# PCB_Telemetria_2020.net
KiCad netlist of a schematic drawn in EAGLE
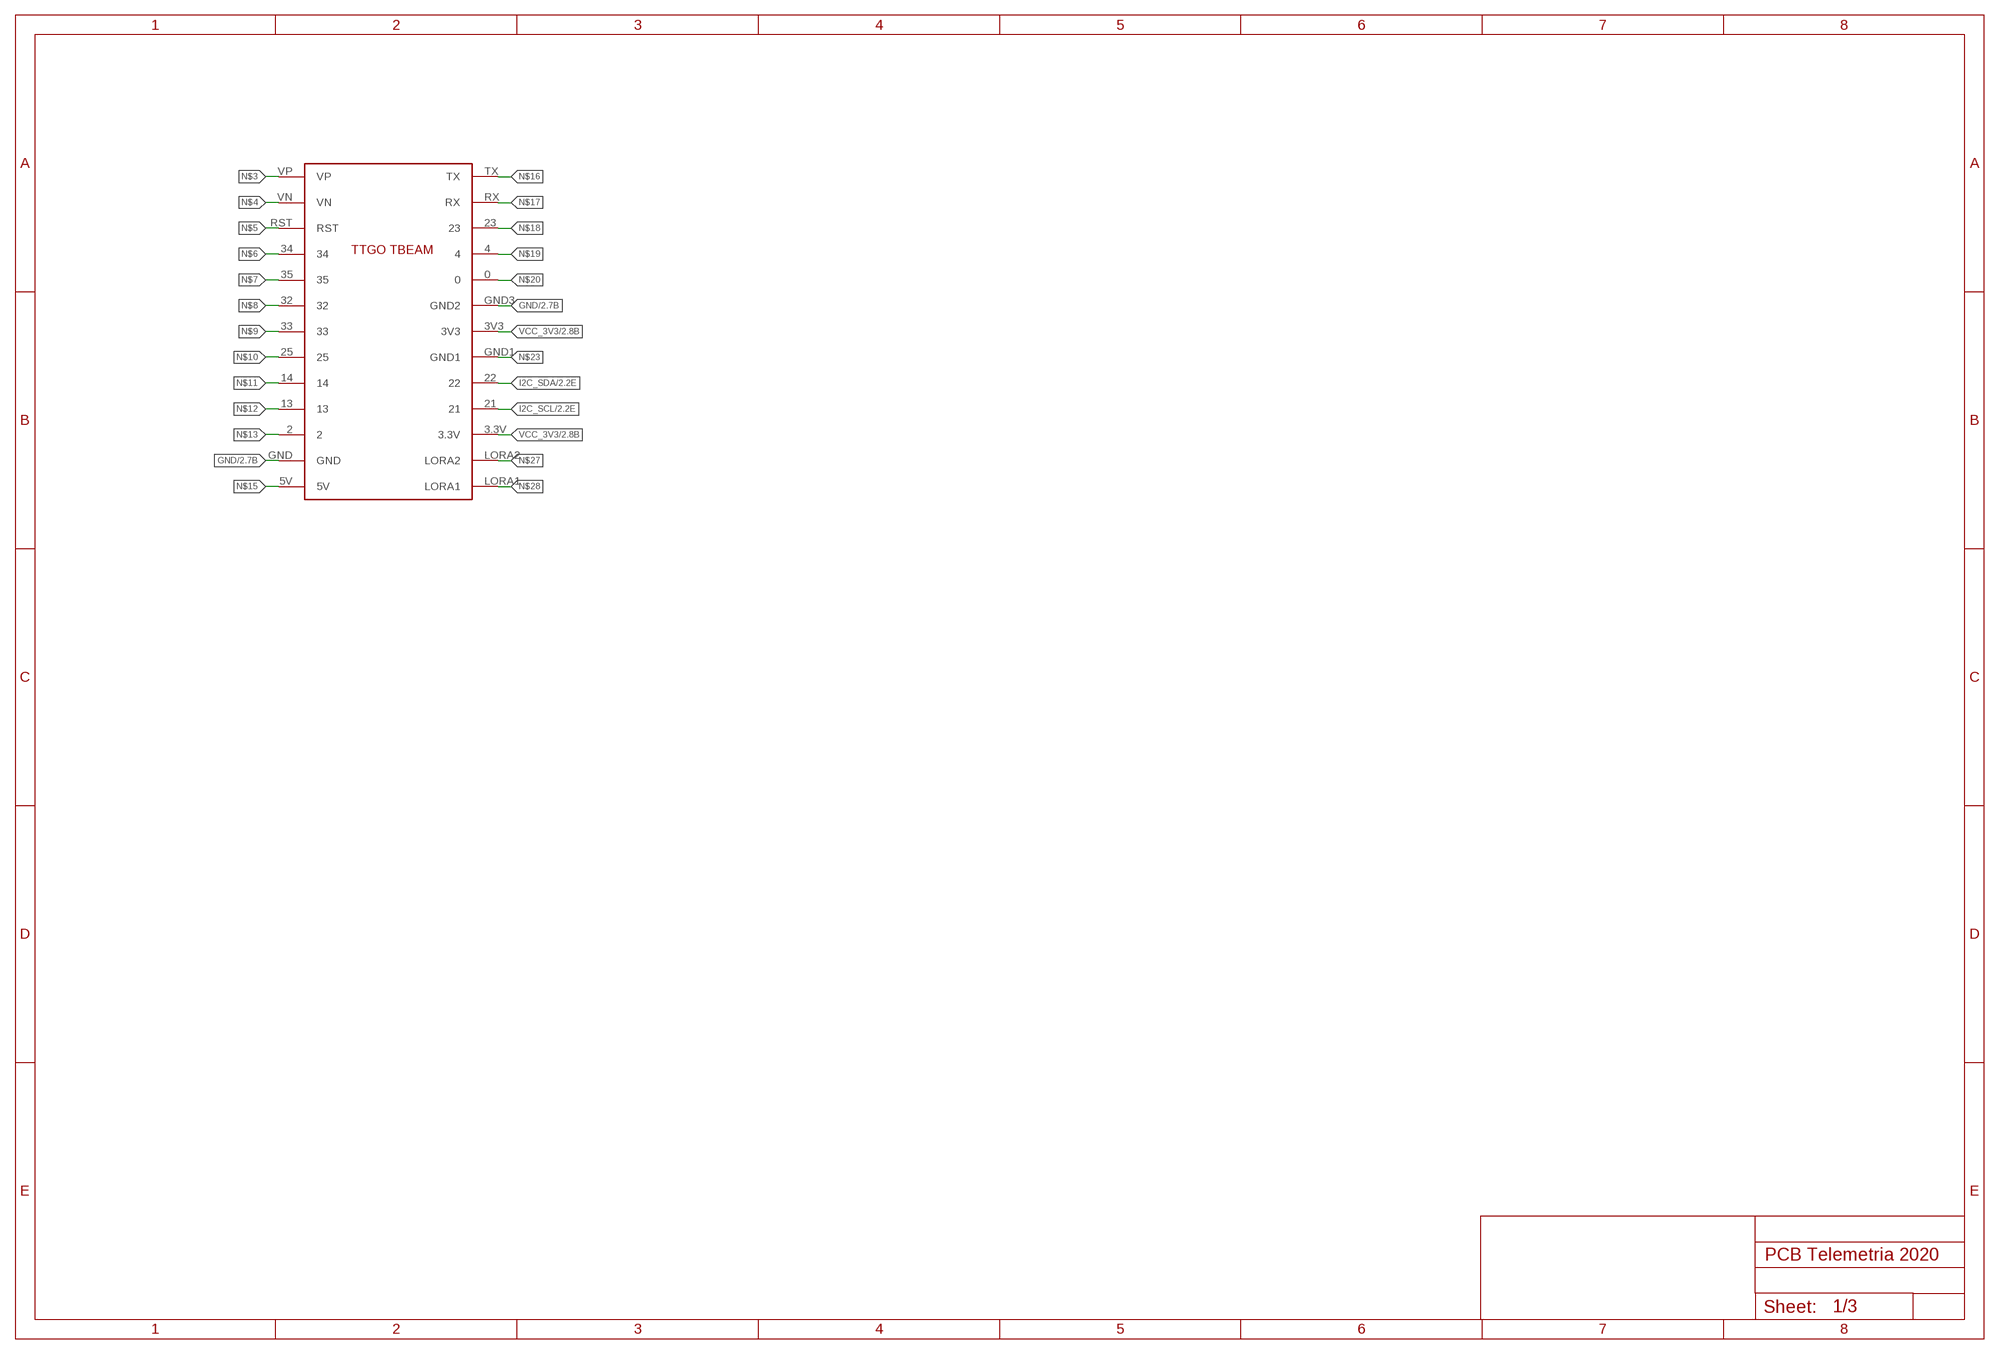
[diagram p0: schematic, sheet 1]
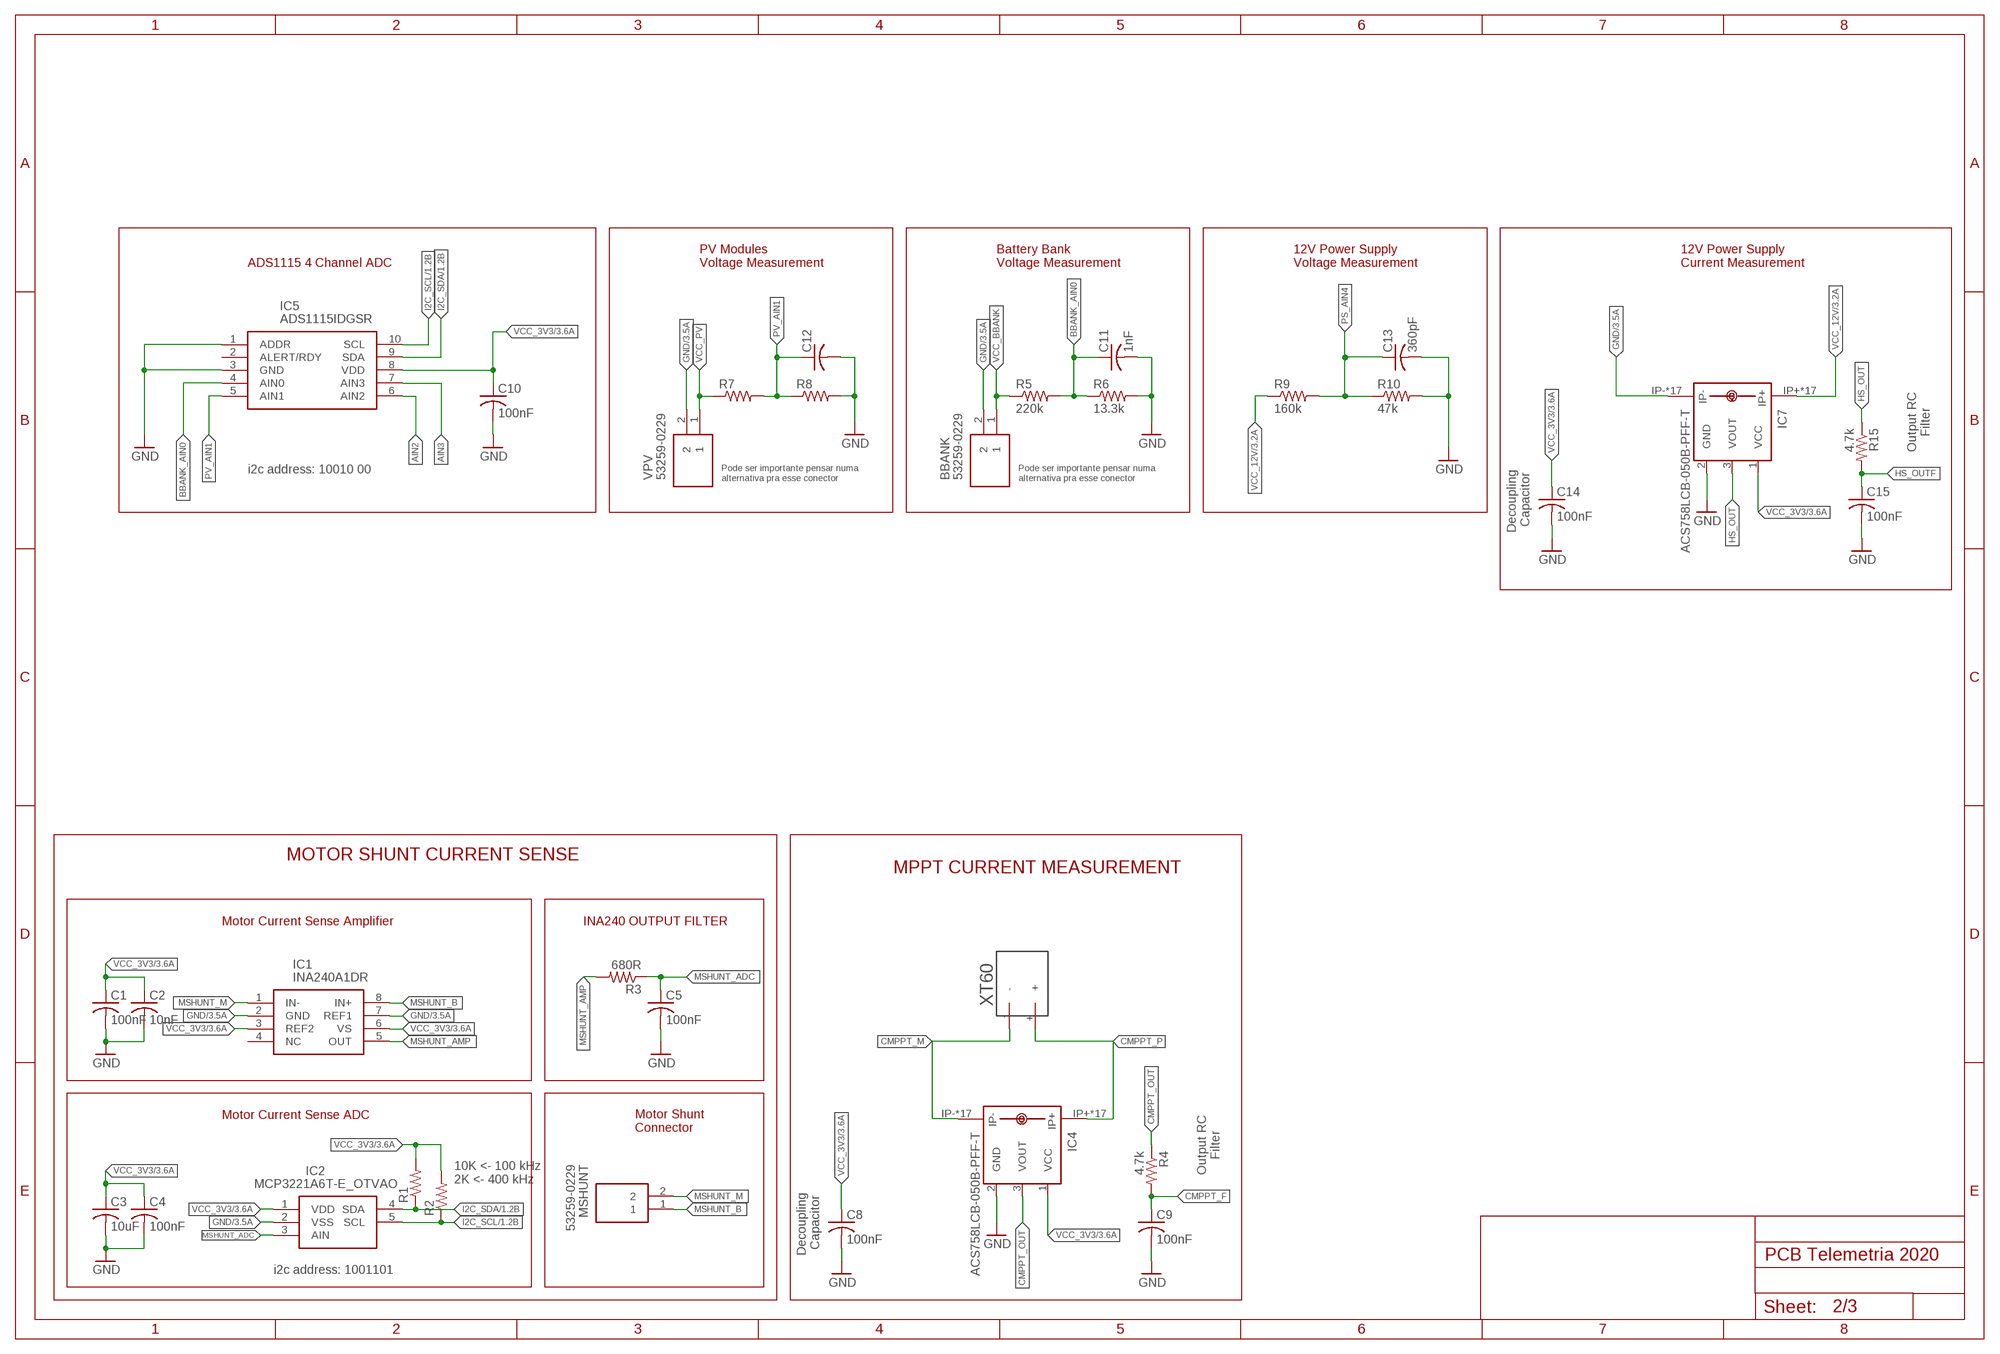
[diagram p1: schematic, sheet 2]
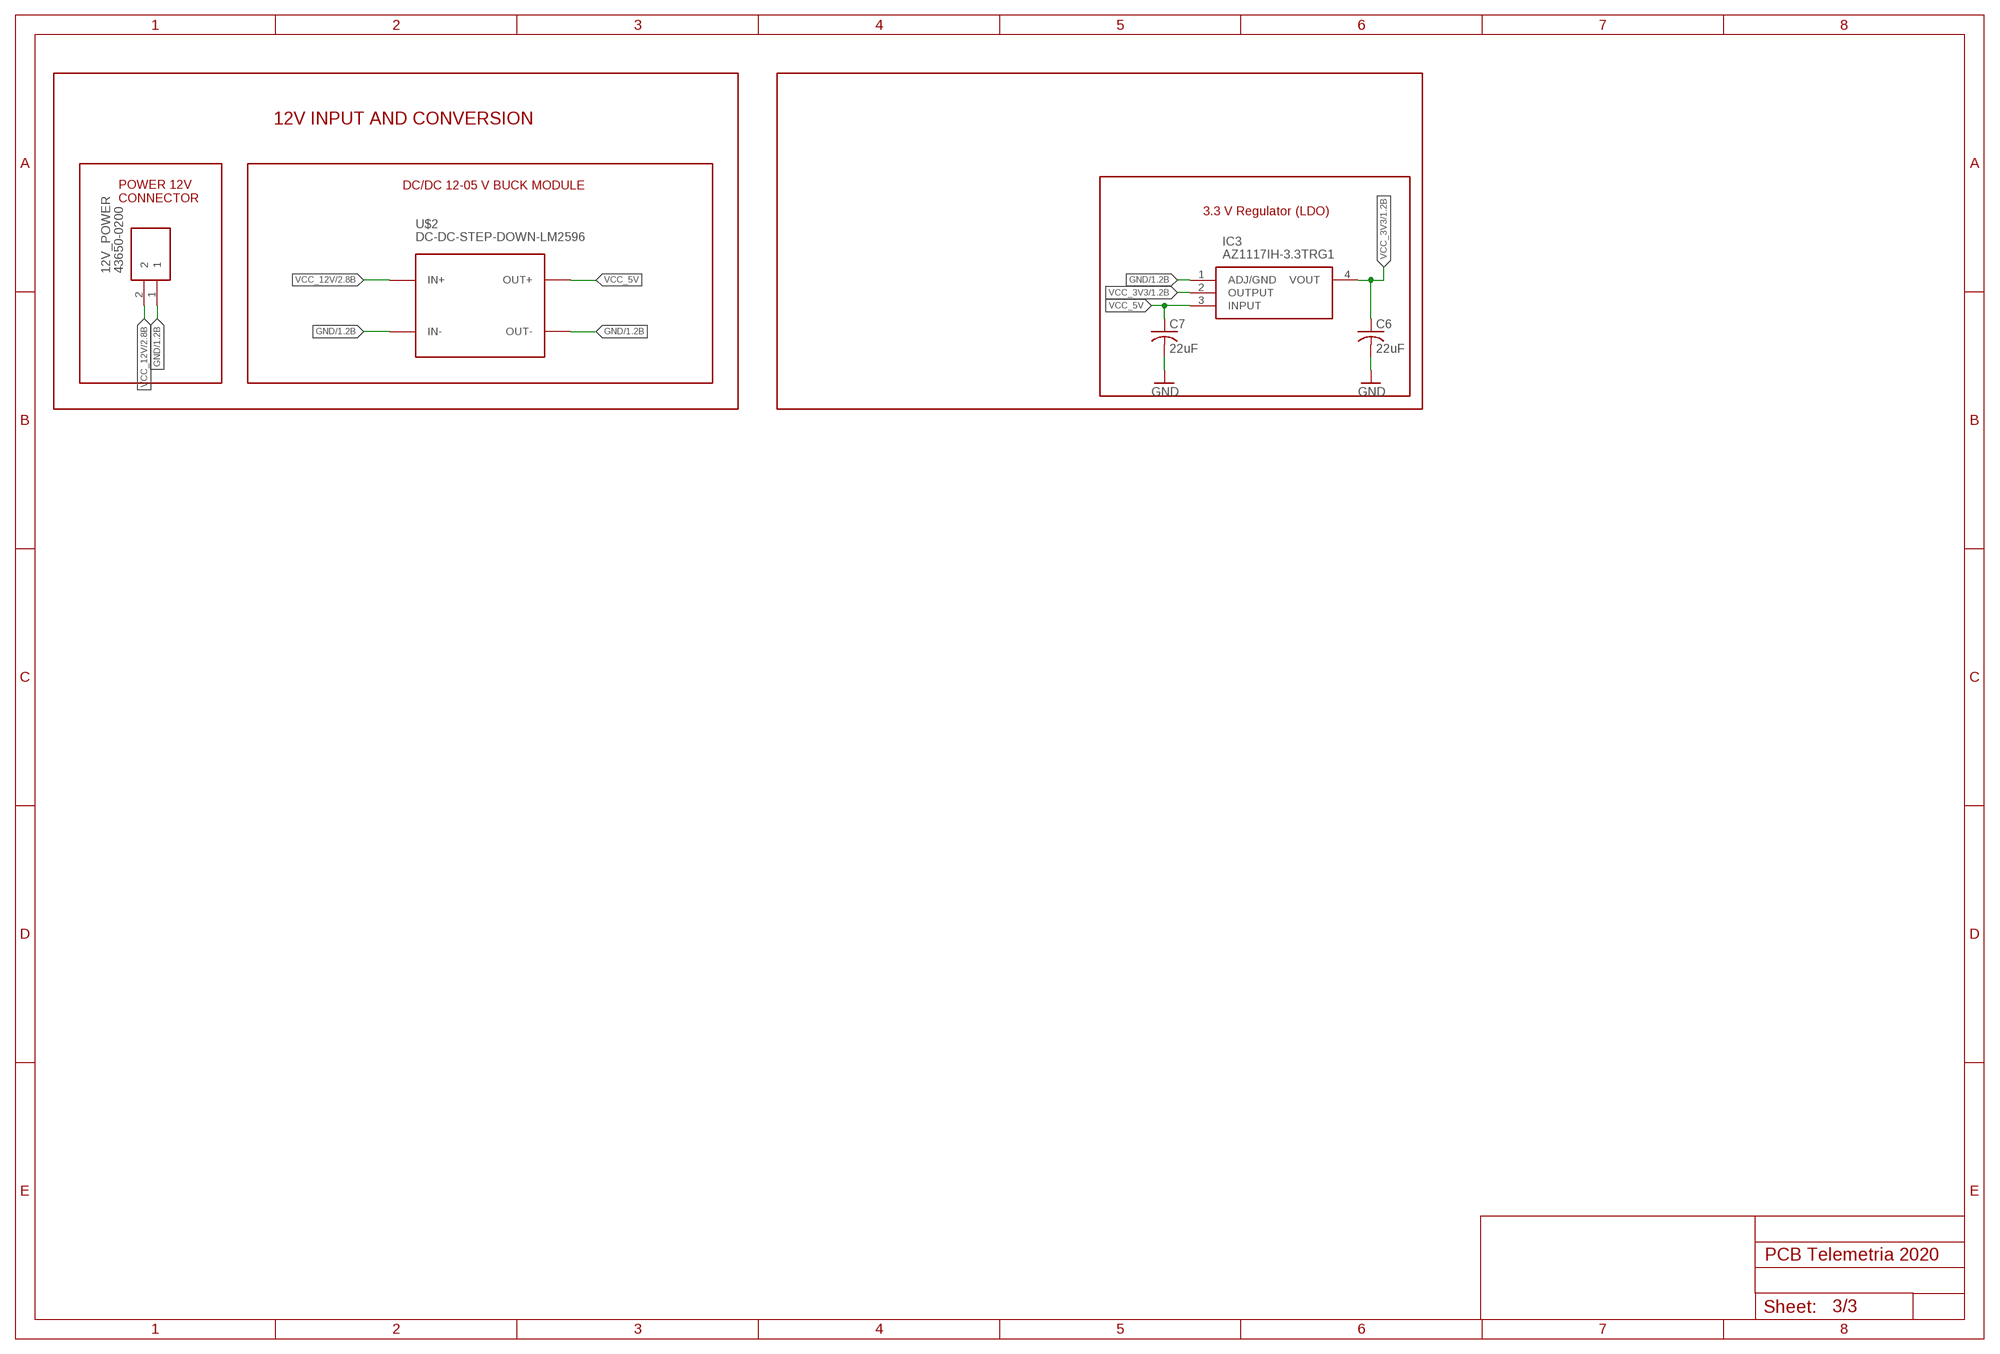
[diagram p2: schematic, sheet 3]

(export (version "E")
  (design (tool "Eeschema 10.0.6"))
  (components
    (comp (ref "BBANK")
      (value "53259-0229")
      (footprint "eagle-import:0532590229")
      (fields (field (name "MOUSER_PART_NUMBER") "538-53259-0229"))
      (libsource (lib "eagle-import") (part "53259-0229"))
    )
    (comp (ref "C1")
      (value "100nF")
      (footprint "eagle-import:C0805")
      (libsource (lib "eagle-import") (part "C-USC0805"))
    )
    (comp (ref "C2")
      (value "10nF")
      (footprint "eagle-import:C0805")
      (libsource (lib "eagle-import") (part "C-USC0805"))
    )
    (comp (ref "C3")
      (value "10uF")
      (footprint "eagle-import:C0805")
      (libsource (lib "eagle-import") (part "C-USC0805"))
    )
    (comp (ref "C4")
      (value "100nF")
      (footprint "eagle-import:C0805")
      (libsource (lib "eagle-import") (part "C-USC0805"))
    )
    (comp (ref "C5")
      (value "100nF")
      (footprint "eagle-import:C0805")
      (libsource (lib "eagle-import") (part "C-USC0805"))
    )
    (comp (ref "C8")
      (value "100nF")
      (footprint "eagle-import:C0805")
      (libsource (lib "eagle-import") (part "C-USC0805"))
    )
    (comp (ref "C9")
      (value "100nF")
      (footprint "eagle-import:C0805")
      (libsource (lib "eagle-import") (part "C-USC0805"))
    )
    (comp (ref "C10")
      (value "100nF")
      (footprint "eagle-import:C0805")
      (libsource (lib "eagle-import") (part "C-USC0805"))
    )
    (comp (ref "C11")
      (value "1nF")
      (footprint "eagle-import:C0805")
      (libsource (lib "eagle-import") (part "C-USC0805"))
    )
    (comp (ref "C12")
      (value "C-USC0805")
      (footprint "eagle-import:C0805")
      (libsource (lib "eagle-import") (part "C-USC0805"))
    )
    (comp (ref "C13")
      (value "360pF")
      (footprint "eagle-import:C0805")
      (libsource (lib "eagle-import") (part "C-USC0805"))
    )
    (comp (ref "C14")
      (value "100nF")
      (footprint "eagle-import:C0805")
      (libsource (lib "eagle-import") (part "C-USC0805"))
    )
    (comp (ref "C15")
      (value "100nF")
      (footprint "eagle-import:C0805")
      (libsource (lib "eagle-import") (part "C-USC0805"))
    )
    (comp (ref "IC1")
      (value "INA240A1DR")
      (footprint "eagle-import:SOIC127P600X175-8N")
      (fields (field (name "MOUSER_PART_NUMBER") "595-INA240A1DR"))
      (libsource (lib "eagle-import") (part "INA240A1DR"))
    )
    (comp (ref "IC2")
      (value "MCP3221A6T-E_OTVAO")
      (footprint "eagle-import:SOT95P280X145-5N")
      (fields
        (field (name "MANUFACTURER_PART_NUMBER") "MCP3221A6T-E/OTVAO")
        (field (name "MOUSER_PART_NUMBER") "579-MCP3221A6TEOTVAO")
      )
      (libsource (lib "eagle-import") (part "MCP3221A6T-E_OTVAO"))
    )
    (comp (ref "IC4")
      (value "ACS758LCB-050B-PFF-T")
      (footprint "eagle-import:CB-PFF")
      (libsource (lib "eagle-import") (part "ACS758LCB-050B-PFF-T"))
    )
    (comp (ref "IC5")
      (value "ADS1115IDGSR")
      (footprint "eagle-import:SOP50P490X110-10N")
      (fields (field (name "MOUSER_PART_NUMBER") "595-ADS1115IDGSR"))
      (libsource (lib "eagle-import") (part "ADS1115IDGSR"))
    )
    (comp (ref "IC7")
      (value "ACS758LCB-050B-PFF-T")
      (footprint "eagle-import:CB-PFF")
      (libsource (lib "eagle-import") (part "ACS758LCB-050B-PFF-T"))
    )
    (comp (ref "MSHUNT")
      (value "53259-0229")
      (footprint "eagle-import:0532590229")
      (fields (field (name "MOUSER_PART_NUMBER") "538-53259-0229"))
      (libsource (lib "eagle-import") (part "53259-0229"))
    )
    (comp (ref "R1")
      (value "R-US_R0805")
      (footprint "eagle-import:R0805")
      (libsource (lib "eagle-import") (part "R-US_R0805"))
    )
    (comp (ref "R2")
      (value "R-US_R0805")
      (footprint "eagle-import:R0805")
      (libsource (lib "eagle-import") (part "R-US_R0805"))
    )
    (comp (ref "R3")
      (value "680R")
      (footprint "eagle-import:R0805")
      (libsource (lib "eagle-import") (part "R-US_R0805"))
    )
    (comp (ref "R4")
      (value "4.7k")
      (footprint "eagle-import:R0805")
      (libsource (lib "eagle-import") (part "R-US_R0805"))
    )
    (comp (ref "R5")
      (value "220k")
      (footprint "eagle-import:R0805")
      (libsource (lib "eagle-import") (part "R-US_R0805"))
    )
    (comp (ref "R6")
      (value "13.3k")
      (footprint "eagle-import:R0805")
      (libsource (lib "eagle-import") (part "R-US_R0805"))
    )
    (comp (ref "R7")
      (value "R-US_R0805")
      (footprint "eagle-import:R0805")
      (libsource (lib "eagle-import") (part "R-US_R0805"))
    )
    (comp (ref "R8")
      (value "R-US_R0805")
      (footprint "eagle-import:R0805")
      (libsource (lib "eagle-import") (part "R-US_R0805"))
    )
    (comp (ref "R9")
      (value "160k")
      (footprint "eagle-import:R0805")
      (libsource (lib "eagle-import") (part "R-US_R0805"))
    )
    (comp (ref "R10")
      (value "47k")
      (footprint "eagle-import:R0805")
      (libsource (lib "eagle-import") (part "R-US_R0805"))
    )
    (comp (ref "R15")
      (value "4.7k")
      (footprint "eagle-import:R0805")
      (libsource (lib "eagle-import") (part "R-US_R0805"))
    )
    (comp (ref "U$3")
      (value "XT60")
      (footprint "eagle-import:XT60")
      (libsource (lib "eagle-import") (part "XT60"))
    )
    (comp (ref "VPV")
      (value "53259-0229")
      (footprint "eagle-import:0532590229")
      (fields (field (name "MOUSER_PART_NUMBER") "538-53259-0229"))
      (libsource (lib "eagle-import") (part "53259-0229"))
    )
    (comp (ref "12V_POWER")
      (value "43650-0200")
      (footprint "eagle-import:43650-0200")
      (fields (field (name "MOUSER_PART_NUMBER") "538-43650-0200"))
      (libsource (lib "eagle-import") (part "43650-0200"))
    )
    (comp (ref "C6")
      (value "22uF")
      (footprint "eagle-import:C0805")
      (libsource (lib "eagle-import") (part "C-USC0805"))
    )
    (comp (ref "C7")
      (value "22uF")
      (footprint "eagle-import:C0805")
      (libsource (lib "eagle-import") (part "C-USC0805"))
    )
    (comp (ref "IC3")
      (value "AZ1117IH-3.3TRG1")
      (footprint "eagle-import:SOT230P700X170-4N")
      (fields (field (name "MOUSER_PART_NUMBER") "621-AZ1117IH-3.3TRG1"))
      (libsource (lib "eagle-import") (part "AZ1117IH-3.3TRG1"))
    )
    (comp (ref "U$2")
      (value "DC-DC-STEP-DOWN-LM2596")
      (footprint "eagle-import:DC-DC-STEP-DOWN-LM2596")
      (libsource (lib "eagle-import") (part "DC-DC-STEP-DOWN-LM2596"))
    )
    (comp (ref "U$1")
      (value "TTGOBEAM")
      (footprint "eagle-import:TTGOBEAM")
      (libsource (lib "eagle-import") (part "TTGOBEAM"))
    )
  )
  (nets
    (net (code "1") (name "AIN2") (class "Default")
      (node (ref "IC5") (pin "6") (pinfunction "AIN2_6") (pintype "bidirectional"))
    )
    (net (code "2") (name "AIN3") (class "Default")
      (node (ref "IC5") (pin "7") (pinfunction "AIN3_7") (pintype "bidirectional"))
    )
    (net (code "3") (name "BBANK_AIN0") (class "Default")
      (node (ref "C11") (pin "1") (pinfunction "1_1") (pintype "passive"))
      (node (ref "IC5") (pin "4") (pinfunction "AIN0_4") (pintype "bidirectional"))
      (node (ref "R5") (pin "2") (pinfunction "2_2") (pintype "passive"))
      (node (ref "R6") (pin "1") (pinfunction "1_1") (pintype "passive"))
    )
    (net (code "4") (name "CMPPT_F") (class "Default")
      (node (ref "C9") (pin "1") (pinfunction "1_1") (pintype "passive"))
      (node (ref "R4") (pin "2") (pinfunction "2_2") (pintype "passive"))
    )
    (net (code "5") (name "CMPPT_M") (class "Default")
      (node (ref "IC4") (pin "IP-") (pinfunction "IP-_IP-") (pintype "passive"))
      (node (ref "IC4") (pin "IP-@10") (pinfunction "IP-_IP-@10") (pintype "passive"))
      (node (ref "IC4") (pin "IP-@11") (pinfunction "IP-_IP-@11") (pintype "passive"))
      (node (ref "IC4") (pin "IP-@12") (pinfunction "IP-_IP-@12") (pintype "passive"))
      (node (ref "IC4") (pin "IP-@13") (pinfunction "IP-_IP-@13") (pintype "passive"))
      (node (ref "IC4") (pin "IP-@14") (pinfunction "IP-_IP-@14") (pintype "passive"))
      (node (ref "IC4") (pin "IP-@15") (pinfunction "IP-_IP-@15") (pintype "passive"))
      (node (ref "IC4") (pin "IP-@16") (pinfunction "IP-_IP-@16") (pintype "passive"))
      (node (ref "IC4") (pin "IP-@17") (pinfunction "IP-_IP-@17") (pintype "passive"))
      (node (ref "IC4") (pin "IP-@2") (pinfunction "IP-_IP-@2") (pintype "passive"))
      (node (ref "IC4") (pin "IP-@3") (pinfunction "IP-_IP-@3") (pintype "passive"))
      (node (ref "IC4") (pin "IP-@4") (pinfunction "IP-_IP-@4") (pintype "passive"))
      (node (ref "IC4") (pin "IP-@5") (pinfunction "IP-_IP-@5") (pintype "passive"))
      (node (ref "IC4") (pin "IP-@6") (pinfunction "IP-_IP-@6") (pintype "passive"))
      (node (ref "IC4") (pin "IP-@7") (pinfunction "IP-_IP-@7") (pintype "passive"))
      (node (ref "IC4") (pin "IP-@8") (pinfunction "IP-_IP-@8") (pintype "passive"))
      (node (ref "IC4") (pin "IP-@9") (pinfunction "IP-_IP-@9") (pintype "passive"))
      (node (ref "U$3") (pin "-") (pinfunction "-_-") (pintype "bidirectional"))
    )
    (net (code "6") (name "CMPPT_OUT") (class "Default")
      (node (ref "IC4") (pin "3") (pinfunction "VOUT_3") (pintype "output"))
      (node (ref "R4") (pin "1") (pinfunction "1_1") (pintype "passive"))
    )
    (net (code "7") (name "CMPPT_P") (class "Default")
      (node (ref "IC4") (pin "IP+") (pinfunction "IP+_IP+") (pintype "passive"))
      (node (ref "IC4") (pin "IP+@10") (pinfunction "IP+_IP+@10") (pintype "passive"))
      (node (ref "IC4") (pin "IP+@11") (pinfunction "IP+_IP+@11") (pintype "passive"))
      (node (ref "IC4") (pin "IP+@12") (pinfunction "IP+_IP+@12") (pintype "passive"))
      (node (ref "IC4") (pin "IP+@13") (pinfunction "IP+_IP+@13") (pintype "passive"))
      (node (ref "IC4") (pin "IP+@14") (pinfunction "IP+_IP+@14") (pintype "passive"))
      (node (ref "IC4") (pin "IP+@15") (pinfunction "IP+_IP+@15") (pintype "passive"))
      (node (ref "IC4") (pin "IP+@16") (pinfunction "IP+_IP+@16") (pintype "passive"))
      (node (ref "IC4") (pin "IP+@17") (pinfunction "IP+_IP+@17") (pintype "passive"))
      (node (ref "IC4") (pin "IP+@2") (pinfunction "IP+_IP+@2") (pintype "passive"))
      (node (ref "IC4") (pin "IP+@3") (pinfunction "IP+_IP+@3") (pintype "passive"))
      (node (ref "IC4") (pin "IP+@4") (pinfunction "IP+_IP+@4") (pintype "passive"))
      (node (ref "IC4") (pin "IP+@5") (pinfunction "IP+_IP+@5") (pintype "passive"))
      (node (ref "IC4") (pin "IP+@6") (pinfunction "IP+_IP+@6") (pintype "passive"))
      (node (ref "IC4") (pin "IP+@7") (pinfunction "IP+_IP+@7") (pintype "passive"))
      (node (ref "IC4") (pin "IP+@8") (pinfunction "IP+_IP+@8") (pintype "passive"))
      (node (ref "IC4") (pin "IP+@9") (pinfunction "IP+_IP+@9") (pintype "passive"))
      (node (ref "U$3") (pin "+") (pinfunction "+_+") (pintype "bidirectional"))
    )
    (net (code "8") (name "GND") (class "Default")
      (node (ref "12V_POWER") (pin "1") (pinfunction "1_1") (pintype "bidirectional"))
      (node (ref "BBANK") (pin "2") (pinfunction "2_2") (pintype "bidirectional"))
      (node (ref "C1") (pin "2") (pinfunction "2_2") (pintype "passive"))
      (node (ref "C10") (pin "2") (pinfunction "2_2") (pintype "passive"))
      (node (ref "C11") (pin "2") (pinfunction "2_2") (pintype "passive"))
      (node (ref "C12") (pin "2") (pinfunction "2_2") (pintype "passive"))
      (node (ref "C13") (pin "2") (pinfunction "2_2") (pintype "passive"))
      (node (ref "C14") (pin "2") (pinfunction "2_2") (pintype "passive"))
      (node (ref "C15") (pin "2") (pinfunction "2_2") (pintype "passive"))
      (node (ref "C2") (pin "2") (pinfunction "2_2") (pintype "passive"))
      (node (ref "C3") (pin "2") (pinfunction "2_2") (pintype "passive"))
      (node (ref "C4") (pin "2") (pinfunction "2_2") (pintype "passive"))
      (node (ref "C5") (pin "2") (pinfunction "2_2") (pintype "passive"))
      (node (ref "C6") (pin "2") (pinfunction "2_2") (pintype "passive"))
      (node (ref "C7") (pin "2") (pinfunction "2_2") (pintype "passive"))
      (node (ref "C8") (pin "2") (pinfunction "2_2") (pintype "passive"))
      (node (ref "C9") (pin "2") (pinfunction "2_2") (pintype "passive"))
      (node (ref "IC1") (pin "2") (pinfunction "GND_2") (pintype "bidirectional"))
      (node (ref "IC1") (pin "7") (pinfunction "REF1_7") (pintype "bidirectional"))
      (node (ref "IC2") (pin "2") (pinfunction "VSS_2") (pintype "bidirectional"))
      (node (ref "IC3") (pin "1") (pinfunction "ADJ/GND_1") (pintype "bidirectional"))
      (node (ref "IC4") (pin "2") (pinfunction "GND_2") (pintype "power_in"))
      (node (ref "IC5") (pin "1") (pinfunction "ADDR_1") (pintype "bidirectional"))
      (node (ref "IC5") (pin "3") (pinfunction "GND_3") (pintype "bidirectional"))
      (node (ref "IC7") (pin "2") (pinfunction "GND_2") (pintype "power_in"))
      (node (ref "IC7") (pin "IP-") (pinfunction "IP-_IP-") (pintype "passive"))
      (node (ref "IC7") (pin "IP-@10") (pinfunction "IP-_IP-@10") (pintype "passive"))
      (node (ref "IC7") (pin "IP-@11") (pinfunction "IP-_IP-@11") (pintype "passive"))
      (node (ref "IC7") (pin "IP-@12") (pinfunction "IP-_IP-@12") (pintype "passive"))
      (node (ref "IC7") (pin "IP-@13") (pinfunction "IP-_IP-@13") (pintype "passive"))
      (node (ref "IC7") (pin "IP-@14") (pinfunction "IP-_IP-@14") (pintype "passive"))
      (node (ref "IC7") (pin "IP-@15") (pinfunction "IP-_IP-@15") (pintype "passive"))
      (node (ref "IC7") (pin "IP-@16") (pinfunction "IP-_IP-@16") (pintype "passive"))
      (node (ref "IC7") (pin "IP-@17") (pinfunction "IP-_IP-@17") (pintype "passive"))
      (node (ref "IC7") (pin "IP-@2") (pinfunction "IP-_IP-@2") (pintype "passive"))
      (node (ref "IC7") (pin "IP-@3") (pinfunction "IP-_IP-@3") (pintype "passive"))
      (node (ref "IC7") (pin "IP-@4") (pinfunction "IP-_IP-@4") (pintype "passive"))
      (node (ref "IC7") (pin "IP-@5") (pinfunction "IP-_IP-@5") (pintype "passive"))
      (node (ref "IC7") (pin "IP-@6") (pinfunction "IP-_IP-@6") (pintype "passive"))
      (node (ref "IC7") (pin "IP-@7") (pinfunction "IP-_IP-@7") (pintype "passive"))
      (node (ref "IC7") (pin "IP-@8") (pinfunction "IP-_IP-@8") (pintype "passive"))
      (node (ref "IC7") (pin "IP-@9") (pinfunction "IP-_IP-@9") (pintype "passive"))
      (node (ref "R10") (pin "2") (pinfunction "2_2") (pintype "passive"))
      (node (ref "R6") (pin "2") (pinfunction "2_2") (pintype "passive"))
      (node (ref "R8") (pin "2") (pinfunction "2_2") (pintype "passive"))
      (node (ref "U$1") (pin "GND") (pinfunction "GND_GND") (pintype "bidirectional"))
      (node (ref "U$1") (pin "GND3") (pinfunction "GND2_GND3") (pintype "bidirectional"))
      (node (ref "U$2") (pin "IN-") (pinfunction "IN-_IN-") (pintype "bidirectional"))
      (node (ref "U$2") (pin "OUT-") (pinfunction "OUT-_OUT-") (pintype "bidirectional"))
      (node (ref "VPV") (pin "2") (pinfunction "2_2") (pintype "bidirectional"))
    )
    (net (code "9") (name "HS_OUT") (class "Default")
      (node (ref "IC7") (pin "3") (pinfunction "VOUT_3") (pintype "output"))
      (node (ref "R15") (pin "1") (pinfunction "1_1") (pintype "passive"))
    )
    (net (code "10") (name "HS_OUTF") (class "Default")
      (node (ref "C15") (pin "1") (pinfunction "1_1") (pintype "passive"))
      (node (ref "R15") (pin "2") (pinfunction "2_2") (pintype "passive"))
    )
    (net (code "11") (name "I2C_SCL") (class "Default")
      (node (ref "IC2") (pin "5") (pinfunction "SCL_5") (pintype "bidirectional"))
      (node (ref "IC5") (pin "10") (pinfunction "SCL_10") (pintype "bidirectional"))
      (node (ref "R2") (pin "1") (pinfunction "1_1") (pintype "passive"))
      (node (ref "U$1") (pin "21") (pinfunction "21_21") (pintype "bidirectional"))
    )
    (net (code "12") (name "I2C_SDA") (class "Default")
      (node (ref "IC2") (pin "4") (pinfunction "SDA_4") (pintype "bidirectional"))
      (node (ref "IC5") (pin "9") (pinfunction "SDA_9") (pintype "bidirectional"))
      (node (ref "R1") (pin "1") (pinfunction "1_1") (pintype "passive"))
      (node (ref "U$1") (pin "22") (pinfunction "22_22") (pintype "bidirectional"))
    )
    (net (code "13") (name "MSHUNT_ADC") (class "Default")
      (node (ref "C5") (pin "1") (pinfunction "1_1") (pintype "passive"))
      (node (ref "IC2") (pin "3") (pinfunction "AIN_3") (pintype "bidirectional"))
      (node (ref "R3") (pin "1") (pinfunction "1_1") (pintype "passive"))
    )
    (net (code "14") (name "MSHUNT_AMP") (class "Default")
      (node (ref "IC1") (pin "5") (pinfunction "OUT_5") (pintype "bidirectional"))
      (node (ref "R3") (pin "2") (pinfunction "2_2") (pintype "passive"))
    )
    (net (code "15") (name "MSHUNT_B") (class "Default")
      (node (ref "IC1") (pin "8") (pinfunction "IN+_8") (pintype "bidirectional"))
      (node (ref "MSHUNT") (pin "1") (pinfunction "1_1") (pintype "bidirectional"))
    )
    (net (code "16") (name "MSHUNT_M") (class "Default")
      (node (ref "IC1") (pin "1") (pinfunction "IN-_1") (pintype "bidirectional"))
      (node (ref "MSHUNT") (pin "2") (pinfunction "2_2") (pintype "bidirectional"))
    )
    (net (code "17") (name "N$3") (class "Default")
      (node (ref "U$1") (pin "VP") (pinfunction "VP_VP") (pintype "bidirectional"))
    )
    (net (code "18") (name "N$4") (class "Default")
      (node (ref "U$1") (pin "VN") (pinfunction "VN_VN") (pintype "bidirectional"))
    )
    (net (code "19") (name "N$5") (class "Default")
      (node (ref "U$1") (pin "RST") (pinfunction "RST_RST") (pintype "bidirectional"))
    )
    (net (code "20") (name "N$6") (class "Default")
      (node (ref "U$1") (pin "34") (pinfunction "34_34") (pintype "bidirectional"))
    )
    (net (code "21") (name "N$7") (class "Default")
      (node (ref "U$1") (pin "35") (pinfunction "35_35") (pintype "bidirectional"))
    )
    (net (code "22") (name "N$8") (class "Default")
      (node (ref "U$1") (pin "32") (pinfunction "32_32") (pintype "bidirectional"))
    )
    (net (code "23") (name "N$9") (class "Default")
      (node (ref "U$1") (pin "33") (pinfunction "33_33") (pintype "bidirectional"))
    )
    (net (code "24") (name "N$10") (class "Default")
      (node (ref "U$1") (pin "25") (pinfunction "25_25") (pintype "bidirectional"))
    )
    (net (code "25") (name "N$11") (class "Default")
      (node (ref "U$1") (pin "14") (pinfunction "14_14") (pintype "bidirectional"))
    )
    (net (code "26") (name "N$12") (class "Default")
      (node (ref "U$1") (pin "13") (pinfunction "13_13") (pintype "bidirectional"))
    )
    (net (code "27") (name "N$13") (class "Default")
      (node (ref "U$1") (pin "2") (pinfunction "2_2") (pintype "bidirectional"))
    )
    (net (code "28") (name "N$15") (class "Default")
      (node (ref "U$1") (pin "5V") (pinfunction "5V_5V") (pintype "bidirectional"))
    )
    (net (code "29") (name "N$16") (class "Default")
      (node (ref "U$1") (pin "TX") (pinfunction "TX_TX") (pintype "bidirectional"))
    )
    (net (code "30") (name "N$17") (class "Default")
      (node (ref "U$1") (pin "RX") (pinfunction "RX_RX") (pintype "bidirectional"))
    )
    (net (code "31") (name "N$18") (class "Default")
      (node (ref "U$1") (pin "23") (pinfunction "23_23") (pintype "bidirectional"))
    )
    (net (code "32") (name "N$19") (class "Default")
      (node (ref "U$1") (pin "4") (pinfunction "4_4") (pintype "bidirectional"))
    )
    (net (code "33") (name "N$20") (class "Default")
      (node (ref "U$1") (pin "0") (pinfunction "0_0") (pintype "bidirectional"))
    )
    (net (code "34") (name "N$23") (class "Default")
      (node (ref "U$1") (pin "GND1") (pinfunction "GND1_GND1") (pintype "bidirectional"))
    )
    (net (code "35") (name "N$27") (class "Default")
      (node (ref "U$1") (pin "LORA2") (pinfunction "LORA2_LORA2") (pintype "bidirectional"))
    )
    (net (code "36") (name "N$28") (class "Default")
      (node (ref "U$1") (pin "LORA1") (pinfunction "LORA1_LORA1") (pintype "bidirectional"))
    )
    (net (code "37") (name "PS_AIN4") (class "Default")
      (node (ref "C13") (pin "1") (pinfunction "1_1") (pintype "passive"))
      (node (ref "R10") (pin "1") (pinfunction "1_1") (pintype "passive"))
      (node (ref "R9") (pin "2") (pinfunction "2_2") (pintype "passive"))
    )
    (net (code "38") (name "PV_AIN1") (class "Default")
      (node (ref "C12") (pin "1") (pinfunction "1_1") (pintype "passive"))
      (node (ref "IC5") (pin "5") (pinfunction "AIN1_5") (pintype "bidirectional"))
      (node (ref "R7") (pin "2") (pinfunction "2_2") (pintype "passive"))
      (node (ref "R8") (pin "1") (pinfunction "1_1") (pintype "passive"))
    )
    (net (code "39") (name "VCC_3V3") (class "Default")
      (node (ref "C1") (pin "1") (pinfunction "1_1") (pintype "passive"))
      (node (ref "C10") (pin "1") (pinfunction "1_1") (pintype "passive"))
      (node (ref "C14") (pin "1") (pinfunction "1_1") (pintype "passive"))
      (node (ref "C2") (pin "1") (pinfunction "1_1") (pintype "passive"))
      (node (ref "C3") (pin "1") (pinfunction "1_1") (pintype "passive"))
      (node (ref "C4") (pin "1") (pinfunction "1_1") (pintype "passive"))
      (node (ref "C6") (pin "1") (pinfunction "1_1") (pintype "passive"))
      (node (ref "C8") (pin "1") (pinfunction "1_1") (pintype "passive"))
      (node (ref "IC1") (pin "3") (pinfunction "REF2_3") (pintype "bidirectional"))
      (node (ref "IC1") (pin "6") (pinfunction "VS_6") (pintype "bidirectional"))
      (node (ref "IC2") (pin "1") (pinfunction "VDD_1") (pintype "bidirectional"))
      (node (ref "IC3") (pin "2") (pinfunction "OUTPUT_2") (pintype "bidirectional"))
      (node (ref "IC3") (pin "4") (pinfunction "VOUT_4") (pintype "bidirectional"))
      (node (ref "IC4") (pin "1") (pinfunction "VCC_1") (pintype "power_in"))
      (node (ref "IC5") (pin "8") (pinfunction "VDD_8") (pintype "bidirectional"))
      (node (ref "IC7") (pin "1") (pinfunction "VCC_1") (pintype "power_in"))
      (node (ref "R1") (pin "2") (pinfunction "2_2") (pintype "passive"))
      (node (ref "R2") (pin "2") (pinfunction "2_2") (pintype "passive"))
      (node (ref "U$1") (pin "3.3V") (pinfunction "3.3V_3.3V") (pintype "bidirectional"))
      (node (ref "U$1") (pin "3V3") (pinfunction "3V3_3V3") (pintype "bidirectional"))
    )
    (net (code "40") (name "VCC_5V") (class "Default")
      (node (ref "C7") (pin "1") (pinfunction "1_1") (pintype "passive"))
      (node (ref "IC3") (pin "3") (pinfunction "INPUT_3") (pintype "bidirectional"))
      (node (ref "U$2") (pin "OUT+") (pinfunction "OUT+_OUT+") (pintype "bidirectional"))
    )
    (net (code "41") (name "VCC_12V") (class "Default")
      (node (ref "12V_POWER") (pin "2") (pinfunction "2_2") (pintype "bidirectional"))
      (node (ref "IC7") (pin "IP+") (pinfunction "IP+_IP+") (pintype "passive"))
      (node (ref "IC7") (pin "IP+@10") (pinfunction "IP+_IP+@10") (pintype "passive"))
      (node (ref "IC7") (pin "IP+@11") (pinfunction "IP+_IP+@11") (pintype "passive"))
      (node (ref "IC7") (pin "IP+@12") (pinfunction "IP+_IP+@12") (pintype "passive"))
      (node (ref "IC7") (pin "IP+@13") (pinfunction "IP+_IP+@13") (pintype "passive"))
      (node (ref "IC7") (pin "IP+@14") (pinfunction "IP+_IP+@14") (pintype "passive"))
      (node (ref "IC7") (pin "IP+@15") (pinfunction "IP+_IP+@15") (pintype "passive"))
      (node (ref "IC7") (pin "IP+@16") (pinfunction "IP+_IP+@16") (pintype "passive"))
      (node (ref "IC7") (pin "IP+@17") (pinfunction "IP+_IP+@17") (pintype "passive"))
      (node (ref "IC7") (pin "IP+@2") (pinfunction "IP+_IP+@2") (pintype "passive"))
      (node (ref "IC7") (pin "IP+@3") (pinfunction "IP+_IP+@3") (pintype "passive"))
      (node (ref "IC7") (pin "IP+@4") (pinfunction "IP+_IP+@4") (pintype "passive"))
      (node (ref "IC7") (pin "IP+@5") (pinfunction "IP+_IP+@5") (pintype "passive"))
      (node (ref "IC7") (pin "IP+@6") (pinfunction "IP+_IP+@6") (pintype "passive"))
      (node (ref "IC7") (pin "IP+@7") (pinfunction "IP+_IP+@7") (pintype "passive"))
      (node (ref "IC7") (pin "IP+@8") (pinfunction "IP+_IP+@8") (pintype "passive"))
      (node (ref "IC7") (pin "IP+@9") (pinfunction "IP+_IP+@9") (pintype "passive"))
      (node (ref "R9") (pin "1") (pinfunction "1_1") (pintype "passive"))
      (node (ref "U$2") (pin "IN+") (pinfunction "IN+_IN+") (pintype "bidirectional"))
    )
    (net (code "42") (name "VCC_BBANK") (class "Default")
      (node (ref "BBANK") (pin "1") (pinfunction "1_1") (pintype "bidirectional"))
      (node (ref "R5") (pin "1") (pinfunction "1_1") (pintype "passive"))
    )
    (net (code "43") (name "VCC_PV") (class "Default")
      (node (ref "R7") (pin "1") (pinfunction "1_1") (pintype "passive"))
      (node (ref "VPV") (pin "1") (pinfunction "1_1") (pintype "bidirectional"))
    )
    (net (code "44") (name "unconnected-(IC1-NC-Pad4)") (class "Default")
      (node (ref "IC1") (pin "4") (pinfunction "NC_4") (pintype "no_connect"))
    )
    (net (code "45") (name "unconnected-(IC5-ALERT{slash}RDY-Pad2)") (class "Default")
      (node (ref "IC5") (pin "2") (pinfunction "ALERT/RDY_2") (pintype "bidirectional"))
    )
  )
)
